# H03R0x_Frontend.net
KiCad netlist of a schematic drawn in Altium Designer
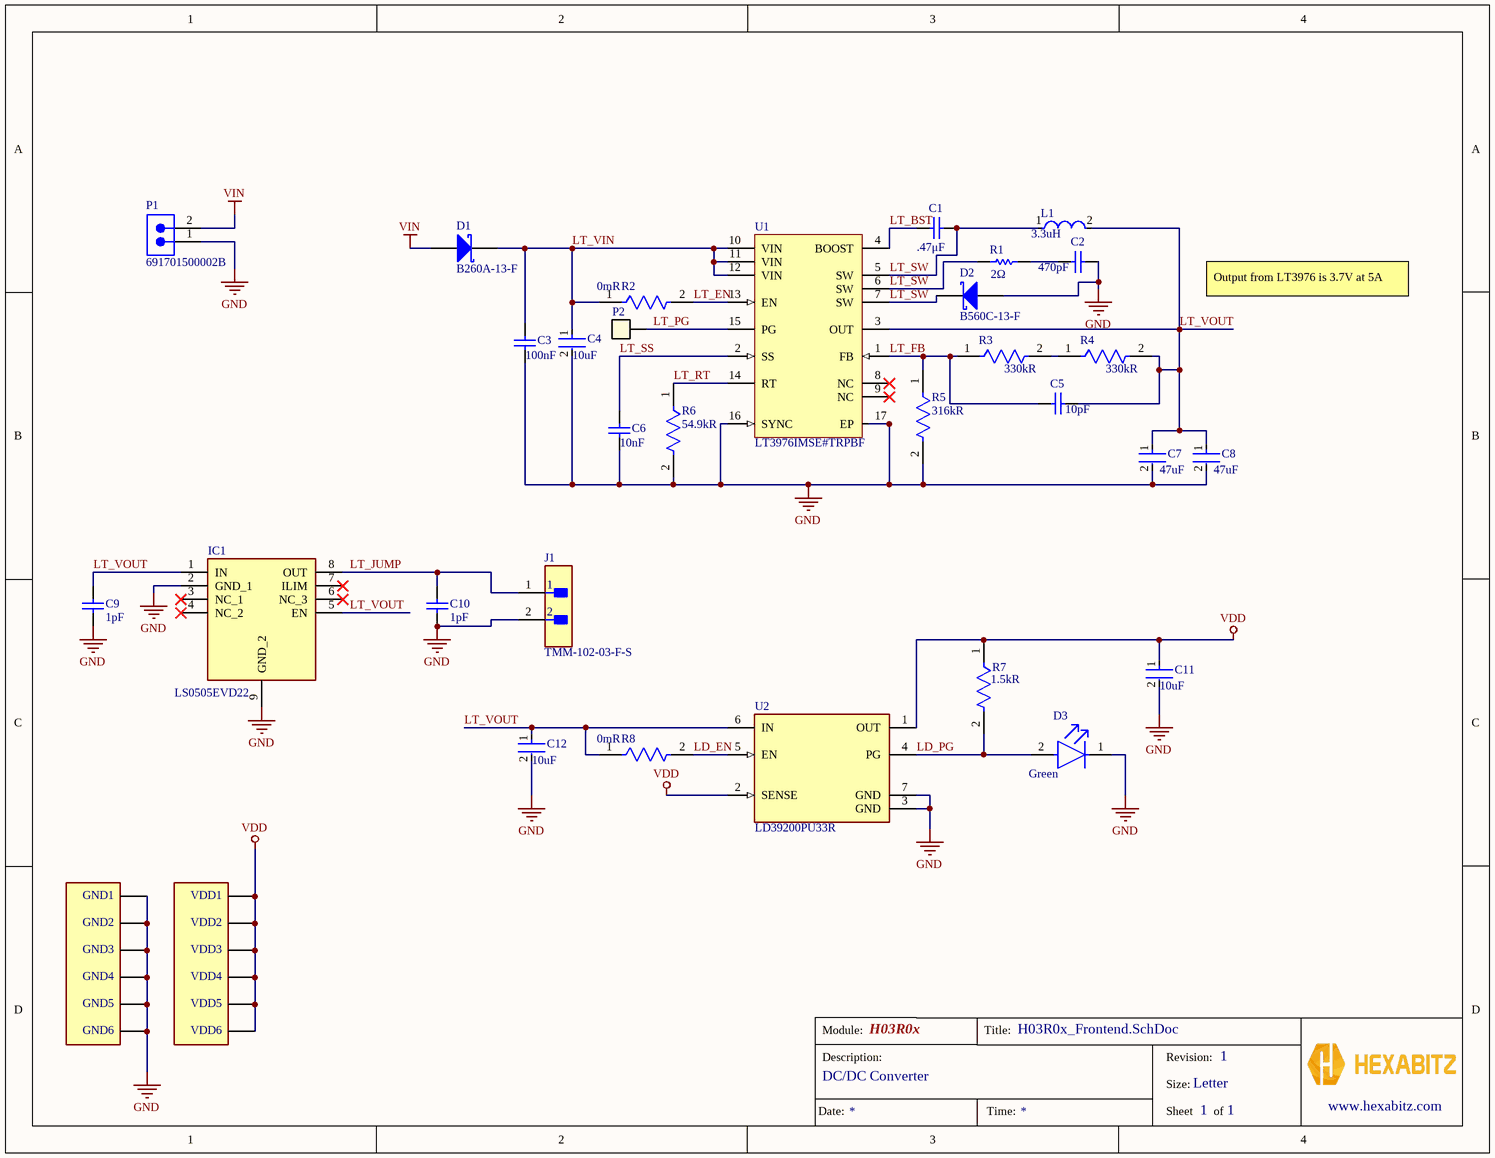
[diagram p0: H03R0x_Frontend.SchDoc]

(export (version "E")
  (design (tool "Eeschema 10.0.6"))
  (components
    (comp (ref "C1")
      (value "VJ0805Y474KXQRW1BC")
      (footprint "CAPC2013X145X50LL20T20")
      (fields (field (name "MANUFACTURER") "Vitramon") (field (name "CAPACITANCE") ".47μF"))
      (libsource (lib "Altium Content Vault") (part "CAP"))
    )
    (comp (ref "C2")
      (value "08055C471KAT4A")
      (footprint "CAPC2013X94X50NL20T25")
      (fields (field (name "MANUFACTURER") "AVX Interconnect / Elco") (field (name "CAPACITANCE") "470pF"))
      (libsource (lib "Altium Content Vault") (part "CAP"))
    )
    (comp (ref "C3")
      (value "08055C104KAZ2A")
      (footprint "CAPC2013X94X50NL20T25")
      (fields (field (name "MANUFACTURER") "AVX Interconnect / Elco") (field (name "CAPACITANCE") "100nF"))
      (libsource (lib "Altium Content Vault") (part "CAP"))
    )
    (comp (ref "C4")
      (value "GRM32ER71H106KA12L")
      (footprint "FP-GRM32-MFG")
      (description "CAP CER 10UF 50V X7R 1210")
      (fields
        (field (name "TOLERANCE") "10%")
        (field (name "MANUFACTURER") "Murata")
        (field (name "CAPACITANCE") "10uF")
      )
      (libsource (lib "Altium Content Vault") (part "11868f565c42a9108669ba33697ecf6"))
    )
    (comp (ref "C5")
      (value "08051A100JAT4A")
      (footprint "CAPC2013X94X50LL20T25")
      (fields (field (name "MANUFACTURER") "AVX Interconnect / Elco") (field (name "CAPACITANCE") "10pF"))
      (libsource (lib "Altium Content Vault") (part "CAP"))
    )
    (comp (ref "C6")
      (value "0805YC103MAT2A")
      (footprint "CAPC2013X94X50ML20T25")
      (fields (field (name "MANUFACTURER") "AVX Interconnect / Elco") (field (name "CAPACITANCE") "10nF"))
      (libsource (lib "Altium Content Vault") (part "CAP"))
    )
    (comp (ref "C7")
      (value "GRM32ED71A476KE15L")
      (footprint "FP-GRM32E-0_3-0_2-MFG")
      (description "Chip Multilayer Ceramic Capacitors for General Purpose, 1210, 47uF, X7T, +22%/-33%, 10%, 10V")
      (fields (field (name "TOLERANCE") "10%") (field (name "CAPACITANCE") "47uF"))
      (libsource (lib "Altium Content Vault") (part "02cd4be3c70576c341d710602a673aa"))
    )
    (comp (ref "C8")
      (value "GRM32ED71A476KE15L")
      (footprint "FP-GRM32E-0_3-0_2-MFG")
      (description "Chip Multilayer Ceramic Capacitors for General Purpose, 1210, 47uF, X7T, +22%/-33%, 10%, 10V")
      (fields (field (name "TOLERANCE") "10%") (field (name "CAPACITANCE") "47uF"))
      (libsource (lib "Altium Content Vault") (part "02cd4be3c70576c341d710602a673aa"))
    )
    (comp (ref "C9")
      (value "06032U1R0BAT2A")
      (footprint "CAPC1508X91X25LL25T13")
      (fields (field (name "MANUFACTURER") "AVX Interconnect / Elco") (field (name "CAPACITANCE") "1pF"))
      (libsource (lib "Altium Content Vault") (part "CAP"))
    )
    (comp (ref "C10")
      (value "06032U1R0BAT2A")
      (footprint "CAPC1508X91X25LL25T13")
      (fields (field (name "MANUFACTURER") "AVX Interconnect / Elco") (field (name "CAPACITANCE") "1pF"))
      (libsource (lib "Altium Content Vault") (part "CAP"))
    )
    (comp (ref "C11")
      (value "GRM32ER71H106KA12L")
      (footprint "FP-GRM32-MFG")
      (description "CAP CER 10UF 50V X7R 1210")
      (fields
        (field (name "TOLERANCE") "10%")
        (field (name "MANUFACTURER") "Murata")
        (field (name "CAPACITANCE") "10uF")
      )
      (libsource (lib "Altium Content Vault") (part "11868f565c42a9108669ba33697ecf6"))
    )
    (comp (ref "C12")
      (value "GRM32ER71H106KA12L")
      (footprint "FP-GRM32-MFG")
      (description "CAP CER 10UF 50V X7R 1210")
      (fields
        (field (name "TOLERANCE") "10%")
        (field (name "MANUFACTURER") "Murata")
        (field (name "CAPACITANCE") "10uF")
      )
      (libsource (lib "Altium Content Vault") (part "11868f565c42a9108669ba33697ecf6"))
    )
    (comp (ref "D1")
      (value "B260A-13-F")
      (footprint "DIOD-SMA-2_V")
      (description "Schottky Barrier Rectifier, 60 V, 2 A, -65 to 150 degC, 2-Pin SMA, RoHS, Tape and Reel")
      (fields (field (name "MANUFACTURER") "DiodesIncorporated"))
      (libsource (lib "Altium Content Vault") (part "DSKY-AK-2"))
    )
    (comp (ref "D2")
      (value "B560C-13-F")
      (footprint "DIOD-B5X0C-2_M")
      (description "Schottky Barrier Rectifier, 5 A, 60 V, -55 to 125 degC, 2-Pin SMD, RoHS, Tape and Reel")
      (fields (field (name "MANUFACTURER") "DiodesIncorporated"))
      (libsource (lib "Altium Content Vault") (part "DSKY-KA-2"))
    )
    (comp (ref "D3")
      (value "APHCM2012CGCK-F01")
      (footprint "FP-APHCM2012CGCK-F01-MFG")
      (description "LED GREEN CLEAR CHIP SMD")
      (fields (field (name "ILLUMINATION COLOR") "Green"))
      (libsource (lib "Altium Content Vault") (part "8706943c75ba83719d021d2fdc84c58"))
    )
    (comp (ref "GND1")
      (value "HEXABIT_UART_PORT")
      (footprint "HEXABIT_POWER_PORT_D")
      (libsource (lib "hexabitz_connectors.Library") (part "HEXABIT_POWER_PORT_D"))
    )
    (comp (ref "GND2")
      (value "HEXABIT_UART_PORT")
      (footprint "HEXABIT_POWER_PORT_D")
      (libsource (lib "hexabitz_connectors.Library") (part "HEXABIT_POWER_PORT_D"))
    )
    (comp (ref "GND3")
      (value "HEXABIT_UART_PORT")
      (footprint "HEXABIT_POWER_PORT_D")
      (libsource (lib "hexabitz_connectors.Library") (part "HEXABIT_POWER_PORT_D"))
    )
    (comp (ref "GND4")
      (value "HEXABIT_UART_PORT")
      (footprint "HEXABIT_POWER_PORT_D")
      (libsource (lib "hexabitz_connectors.Library") (part "HEXABIT_POWER_PORT_D"))
    )
    (comp (ref "GND5")
      (value "HEXABIT_UART_PORT")
      (footprint "HEXABIT_POWER_PORT_D")
      (libsource (lib "hexabitz_connectors.Library") (part "HEXABIT_POWER_PORT_D"))
    )
    (comp (ref "GND6")
      (value "HEXABIT_UART_PORT")
      (footprint "HEXABIT_POWER_PORT_D")
      (libsource (lib "hexabitz_connectors.Library") (part "HEXABIT_POWER_PORT_D"))
    )
    (comp (ref "IC1")
      (value "LS0505EVD22")
      (footprint "SamacSys:SON50P200X200X80-9N")
      (description "Integrated Circuit")
      (fields (field (name "MOUSER PART NUMBER") "576-LS0505EVD22"))
      (libsource (lib "*") (part "LS0505EVD22"))
    )
    (comp (ref "J1")
      (value "TMM-102-03-F-S")
      (footprint "FP-TMM-102-03-F-S-MFG")
      (description "CONN HEADER VERT 2POS 2MM")
      (libsource (lib "Altium Content Vault") (part "3bc925449376181038e59eaffc5286c"))
    )
    (comp (ref "L1")
      (value "MLZ2012A3R3WT000")
      (footprint "FP-MLZ2012-0_85-IPC_C")
      (description "Shielded Multilayer Inductor 3.3uH ±20% 450mA 442mΩ SMD 0805")
      (fields (field (name "INDUCTANCE") "3.3uH") (field (name "TOLERANCE") "20%"))
      (libsource (lib "Altium Content Vault") (part "725321dda6339637d4d059423bc1c3c"))
    )
    (comp (ref "P1")
      (value "691701500002B")
      (footprint "691701500002B")
      (libsource (lib "Altium Content Vault") (part "TBL - 1R - 02P - Male"))
    )
    (comp (ref "P2")
      (value "Pad1")
      (footprint "TESTPOINT_1P4MM_SQ")
      (description "Pad  2.5mm *  2.5mm")
      (libsource (lib "Nathan Price") (part "Pad1"))
    )
    (comp (ref "R1")
      (value "CRCW08052R00FNEA")
      (footprint "RESC2013X50X30NL20T20")
      (fields (field (name "MANUFACTURER") "Vishay Dale") (field (name "RESISTANCE") "2Ω"))
      (libsource (lib "Altium Content Vault") (part "RES"))
    )
    (comp (ref "R2")
      (value "RMCF0805ZT0R00")
      (footprint "FP-RMCF0805-MFG")
      (description "RES 0 OHM JUMPER 1/8W 0805")
      (fields (field (name "RESISTANCE") "0mR"))
      (libsource (lib "Altium Content Vault") (part "1029c3af85768c4190bb7ad29bc67b5"))
    )
    (comp (ref "R3")
      (value "CRCW0805330KFKEA")
      (footprint "FP-CRCW0805-e3-MFG")
      (description "RES Thick Film, 330kΩ, 1%, 0.125W, 100ppm/°C, 0805")
      (fields (field (name "RESISTANCE") "330kR") (field (name "TOLERANCE") "1%"))
      (libsource (lib "Altium Content Vault") (part "1029c3af85768c4190bb7ad29bc67b5"))
    )
    (comp (ref "R4")
      (value "CRCW0805330KFKEA")
      (footprint "FP-CRCW0805-e3-MFG")
      (description "RES Thick Film, 330kΩ, 1%, 0.125W, 100ppm/°C, 0805")
      (fields (field (name "RESISTANCE") "330kR") (field (name "TOLERANCE") "1%"))
      (libsource (lib "Altium Content Vault") (part "1029c3af85768c4190bb7ad29bc67b5"))
    )
    (comp (ref "R5")
      (value "RC2012F3163CS")
      (footprint "FP-RC2012-IPC_C")
      (description "Res Thick Film 0805 316kΩ 1% 0.125W ±100ppm/°C Molded SMD T/R")
      (fields (field (name "TOLERANCE") "1%") (field (name "RESISTANCE") "316kR"))
      (libsource (lib "Altium Content Vault") (part "1029c3af85768c4190bb7ad29bc67b5"))
    )
    (comp (ref "R6")
      (value "CR0805-FX-5492ELF")
      (footprint "FP-CR0805-MFG")
      (description "Thick Film Chip Resistors 0805 54.9kΩ 0.125W 1% 100ppm/°C")
      (fields (field (name "RESISTANCE") "54.9kR") (field (name "TOLERANCE") "1%"))
      (libsource (lib "Altium Content Vault") (part "1029c3af85768c4190bb7ad29bc67b5"))
    )
    (comp (ref "R7")
      (value "RMCF0805JT1K50")
      (footprint "FP-RMCF0805-IPC_A")
      (description "1.5kΩ ±5% 0.125W 0805 Thick Film Chip Resistor AEC-Q200 compliant")
      (fields (field (name "TOLERANCE") "5%") (field (name "RESISTANCE") "1.5kR"))
      (libsource (lib "Altium Content Vault") (part "1029c3af85768c4190bb7ad29bc67b5"))
    )
    (comp (ref "R8")
      (value "RMCF0805ZT0R00")
      (footprint "FP-RMCF0805-MFG")
      (description "RES 0 OHM JUMPER 1/8W 0805")
      (fields (field (name "RESISTANCE") "0mR"))
      (libsource (lib "Altium Content Vault") (part "1029c3af85768c4190bb7ad29bc67b5"))
    )
    (comp (ref "U1")
      (value "LT3976IMSE#TRPBF")
      (footprint "LT-MSE-16-EDP_M")
      (description "LT3976 - 40V, 5A, 2MHz Step-Down Switching Regulator with 3.3μA Quiescent Current")
      (libsource (lib "Nathan Price") (part "LT-LT3975_LT3976-MSE-16"))
    )
    (comp (ref "U2")
      (value "LD39200PU33R")
      (footprint "FP-DFN6-7946637-MFG")
      (description "IC REG LINEAR 3.3V 2A 6DFN")
      (libsource (lib "Altium Content Vault") (part "f0cfe00d12cb984572f50007c934a2d"))
    )
    (comp (ref "VDD1")
      (value "HEXABIT_UART_PORT")
      (footprint "HEXABIT_POWER_PORT_U")
      (libsource (lib "hexabitz_connectors.Library") (part "HEXABIT_POWER_PORT_U"))
    )
    (comp (ref "VDD2")
      (value "HEXABIT_UART_PORT")
      (footprint "HEXABIT_POWER_PORT_U")
      (libsource (lib "hexabitz_connectors.Library") (part "HEXABIT_POWER_PORT_U"))
    )
    (comp (ref "VDD3")
      (value "HEXABIT_UART_PORT")
      (footprint "HEXABIT_POWER_PORT_U")
      (libsource (lib "hexabitz_connectors.Library") (part "HEXABIT_POWER_PORT_U"))
    )
    (comp (ref "VDD4")
      (value "HEXABIT_UART_PORT")
      (footprint "HEXABIT_POWER_PORT_U")
      (libsource (lib "hexabitz_connectors.Library") (part "HEXABIT_POWER_PORT_U"))
    )
    (comp (ref "VDD5")
      (value "HEXABIT_UART_PORT")
      (footprint "HEXABIT_POWER_PORT_U")
      (libsource (lib "hexabitz_connectors.Library") (part "HEXABIT_POWER_PORT_U"))
    )
    (comp (ref "VDD6")
      (value "HEXABIT_UART_PORT")
      (footprint "HEXABIT_POWER_PORT_U")
      (libsource (lib "hexabitz_connectors.Library") (part "HEXABIT_POWER_PORT_U"))
    )
  )
  (nets
    (net (code "1") (name "/LD_EN") (class "Default")
      (node (ref "R8") (pin "2") (pinfunction "2_2") (pintype "passive"))
      (node (ref "U2") (pin "5") (pinfunction "EN_5") (pintype "input"))
    )
    (net (code "2") (name "/LD_PG") (class "Default")
      (node (ref "D3") (pin "2") (pinfunction "A_2") (pintype "passive"))
      (node (ref "R7") (pin "2") (pinfunction "2_2") (pintype "passive"))
      (node (ref "U2") (pin "4") (pinfunction "PG_4") (pintype "open_collector"))
    )
    (net (code "3") (name "/LT_BST") (class "Default")
      (node (ref "C1") (pin "2") (pinfunction "2_2") (pintype "passive"))
      (node (ref "U1") (pin "4") (pinfunction "BOOST_4") (pintype "passive"))
    )
    (net (code "4") (name "/LT_EN") (class "Default")
      (node (ref "R2") (pin "2") (pinfunction "2_2") (pintype "passive"))
      (node (ref "U1") (pin "13") (pinfunction "EN_13") (pintype "input"))
    )
    (net (code "5") (name "/LT_FB") (class "Default")
      (node (ref "C5") (pin "1") (pinfunction "1_1") (pintype "passive"))
      (node (ref "R3") (pin "1") (pinfunction "1_1") (pintype "passive"))
      (node (ref "R5") (pin "1") (pinfunction "1_1") (pintype "passive"))
      (node (ref "U1") (pin "1") (pinfunction "FB_1") (pintype "input"))
    )
    (net (code "6") (name "/LT_JUMP") (class "Default")
      (node (ref "C10") (pin "1") (pinfunction "1_1") (pintype "passive"))
      (node (ref "IC1") (pin "8") (pinfunction "OUT_8") (pintype "passive"))
      (node (ref "J1") (pin "1") (pinfunction "1_1") (pintype "passive"))
    )
    (net (code "7") (name "/LT_PG") (class "Default")
      (node (ref "P2") (pin "1") (pinfunction "1_1") (pintype "passive"))
      (node (ref "U1") (pin "15") (pinfunction "PG_15") (pintype "tri_state"))
    )
    (net (code "8") (name "/LT_RT") (class "Default")
      (node (ref "R6") (pin "1") (pinfunction "1_1") (pintype "passive"))
      (node (ref "U1") (pin "14") (pinfunction "RT_14") (pintype "passive"))
    )
    (net (code "9") (name "/LT_SS") (class "Default")
      (node (ref "C6") (pin "1") (pinfunction "1_1") (pintype "passive"))
      (node (ref "U1") (pin "2") (pinfunction "SS_2") (pintype "input"))
    )
    (net (code "10") (name "/LT_SW") (class "Default")
      (node (ref "C1") (pin "1") (pinfunction "1_1") (pintype "passive"))
      (node (ref "D2") (pin "1") (pinfunction "K_1") (pintype "passive"))
      (node (ref "L1") (pin "1") (pinfunction "1_1") (pintype "passive"))
      (node (ref "R1") (pin "2") (pinfunction "2_2") (pintype "passive"))
      (node (ref "U1") (pin "5") (pinfunction "SW_5") (pintype "power_in"))
      (node (ref "U1") (pin "6") (pinfunction "SW_6") (pintype "power_in"))
      (node (ref "U1") (pin "7") (pinfunction "SW_7") (pintype "power_in"))
    )
    (net (code "11") (name "/LT_VIN") (class "Default")
      (node (ref "C3") (pin "1") (pinfunction "1_1") (pintype "passive"))
      (node (ref "C4") (pin "1") (pinfunction "1_1") (pintype "passive"))
      (node (ref "D1") (pin "2") (pinfunction "K_2") (pintype "passive"))
      (node (ref "R2") (pin "1") (pinfunction "1_1") (pintype "passive"))
      (node (ref "U1") (pin "10") (pinfunction "VIN_10") (pintype "power_in"))
      (node (ref "U1") (pin "11") (pinfunction "VIN_11") (pintype "power_in"))
      (node (ref "U1") (pin "12") (pinfunction "VIN_12") (pintype "power_in"))
    )
    (net (code "12") (name "/LT_VOUT") (class "Default")
      (node (ref "C12") (pin "1") (pinfunction "1_1") (pintype "passive"))
      (node (ref "C5") (pin "2") (pinfunction "2_2") (pintype "passive"))
      (node (ref "C7") (pin "1") (pinfunction "1_1") (pintype "passive"))
      (node (ref "C8") (pin "1") (pinfunction "1_1") (pintype "passive"))
      (node (ref "C9") (pin "1") (pinfunction "1_1") (pintype "passive"))
      (node (ref "IC1") (pin "1") (pinfunction "IN_1") (pintype "passive"))
      (node (ref "IC1") (pin "5") (pinfunction "EN_5") (pintype "passive"))
      (node (ref "L1") (pin "2") (pinfunction "2_2") (pintype "passive"))
      (node (ref "R4") (pin "2") (pinfunction "2_2") (pintype "passive"))
      (node (ref "R8") (pin "1") (pinfunction "1_1") (pintype "passive"))
      (node (ref "U1") (pin "3") (pinfunction "OUT_3") (pintype "power_in"))
      (node (ref "U2") (pin "6") (pinfunction "IN_6") (pintype "power_in"))
    )
    (net (code "13") (name "GND") (class "Default")
      (node (ref "C10") (pin "2") (pinfunction "2_2") (pintype "passive"))
      (node (ref "C11") (pin "2") (pinfunction "2_2") (pintype "passive"))
      (node (ref "C12") (pin "2") (pinfunction "2_2") (pintype "passive"))
      (node (ref "C2") (pin "2") (pinfunction "2_2") (pintype "passive"))
      (node (ref "C3") (pin "2") (pinfunction "2_2") (pintype "passive"))
      (node (ref "C4") (pin "2") (pinfunction "2_2") (pintype "passive"))
      (node (ref "C6") (pin "2") (pinfunction "2_2") (pintype "passive"))
      (node (ref "C7") (pin "2") (pinfunction "2_2") (pintype "passive"))
      (node (ref "C8") (pin "2") (pinfunction "2_2") (pintype "passive"))
      (node (ref "C9") (pin "2") (pinfunction "2_2") (pintype "passive"))
      (node (ref "D2") (pin "2") (pinfunction "A_2") (pintype "passive"))
      (node (ref "D3") (pin "1") (pinfunction "C_1") (pintype "passive"))
      (node (ref "GND1") (pin "Pwr_D") (pinfunction "Pwr_D_Pwr_D") (pintype "passive"))
      (node (ref "GND2") (pin "Pwr_D") (pinfunction "Pwr_D_Pwr_D") (pintype "passive"))
      (node (ref "GND3") (pin "Pwr_D") (pinfunction "Pwr_D_Pwr_D") (pintype "passive"))
      (node (ref "GND4") (pin "Pwr_D") (pinfunction "Pwr_D_Pwr_D") (pintype "passive"))
      (node (ref "GND5") (pin "Pwr_D") (pinfunction "Pwr_D_Pwr_D") (pintype "passive"))
      (node (ref "GND6") (pin "Pwr_D") (pinfunction "Pwr_D_Pwr_D") (pintype "passive"))
      (node (ref "IC1") (pin "2") (pinfunction "GND_1_2") (pintype "passive"))
      (node (ref "IC1") (pin "9") (pinfunction "GND_2_9") (pintype "passive"))
      (node (ref "J1") (pin "2") (pinfunction "2_2") (pintype "passive"))
      (node (ref "P1") (pin "1") (pinfunction "1_1") (pintype "passive"))
      (node (ref "R5") (pin "2") (pinfunction "2_2") (pintype "passive"))
      (node (ref "R6") (pin "2") (pinfunction "2_2") (pintype "passive"))
      (node (ref "U1") (pin "16") (pinfunction "SYNC_16") (pintype "input"))
      (node (ref "U1") (pin "17") (pinfunction "EP_17") (pintype "power_in"))
      (node (ref "U2") (pin "3") (pinfunction "GND_3") (pintype "power_in"))
      (node (ref "U2") (pin "7") (pinfunction "GND_7") (pintype "power_in"))
    )
    (net (code "14") (name "Net-(C2-Pad1)") (class "Default")
      (node (ref "C2") (pin "1") (pinfunction "1_1") (pintype "passive"))
      (node (ref "R1") (pin "1") (pinfunction "1_1") (pintype "passive"))
    )
    (net (code "15") (name "Net-(R3-Pad2)") (class "Default")
      (node (ref "R3") (pin "2") (pinfunction "2_2") (pintype "passive"))
      (node (ref "R4") (pin "1") (pinfunction "1_1") (pintype "passive"))
    )
    (net (code "16") (name "VDD") (class "Default")
      (node (ref "C11") (pin "1") (pinfunction "1_1") (pintype "passive"))
      (node (ref "R7") (pin "1") (pinfunction "1_1") (pintype "passive"))
      (node (ref "U2") (pin "1") (pinfunction "OUT_1") (pintype "power_in"))
      (node (ref "U2") (pin "2") (pinfunction "SENSE_2") (pintype "input"))
      (node (ref "VDD1") (pin "Pwr_U") (pinfunction "Pwr_U_Pwr_U") (pintype "passive"))
      (node (ref "VDD2") (pin "Pwr_U") (pinfunction "Pwr_U_Pwr_U") (pintype "passive"))
      (node (ref "VDD3") (pin "Pwr_U") (pinfunction "Pwr_U_Pwr_U") (pintype "passive"))
      (node (ref "VDD4") (pin "Pwr_U") (pinfunction "Pwr_U_Pwr_U") (pintype "passive"))
      (node (ref "VDD5") (pin "Pwr_U") (pinfunction "Pwr_U_Pwr_U") (pintype "passive"))
      (node (ref "VDD6") (pin "Pwr_U") (pinfunction "Pwr_U_Pwr_U") (pintype "passive"))
    )
    (net (code "17") (name "VIN") (class "Default")
      (node (ref "D1") (pin "1") (pinfunction "A_1") (pintype "passive"))
      (node (ref "P1") (pin "2") (pinfunction "2_2") (pintype "passive"))
    )
    (net (code "18") (name "unconnected-(IC1-ILIM-Pad7)") (class "Default")
      (node (ref "IC1") (pin "7") (pinfunction "ILIM_7") (pintype "passive+no_connect"))
    )
    (net (code "19") (name "unconnected-(IC1-NC_1-Pad3)") (class "Default")
      (node (ref "IC1") (pin "3") (pinfunction "NC_1_3") (pintype "passive+no_connect"))
    )
    (net (code "20") (name "unconnected-(IC1-NC_2-Pad4)") (class "Default")
      (node (ref "IC1") (pin "4") (pinfunction "NC_2_4") (pintype "passive+no_connect"))
    )
    (net (code "21") (name "unconnected-(IC1-NC_3-Pad6)") (class "Default")
      (node (ref "IC1") (pin "6") (pinfunction "NC_3_6") (pintype "passive+no_connect"))
    )
    (net (code "22") (name "unconnected-(U1-NC-Pad8)") (class "Default")
      (node (ref "U1") (pin "8") (pinfunction "NC_8") (pintype "passive+no_connect"))
    )
    (net (code "23") (name "unconnected-(U1-NC-Pad9)") (class "Default")
      (node (ref "U1") (pin "9") (pinfunction "NC_9") (pintype "passive+no_connect"))
    )
  )
)
